# Center_Console_-_Raspberry_Pi_Interface.net
KiCad netlist of a schematic drawn in Altium Designer
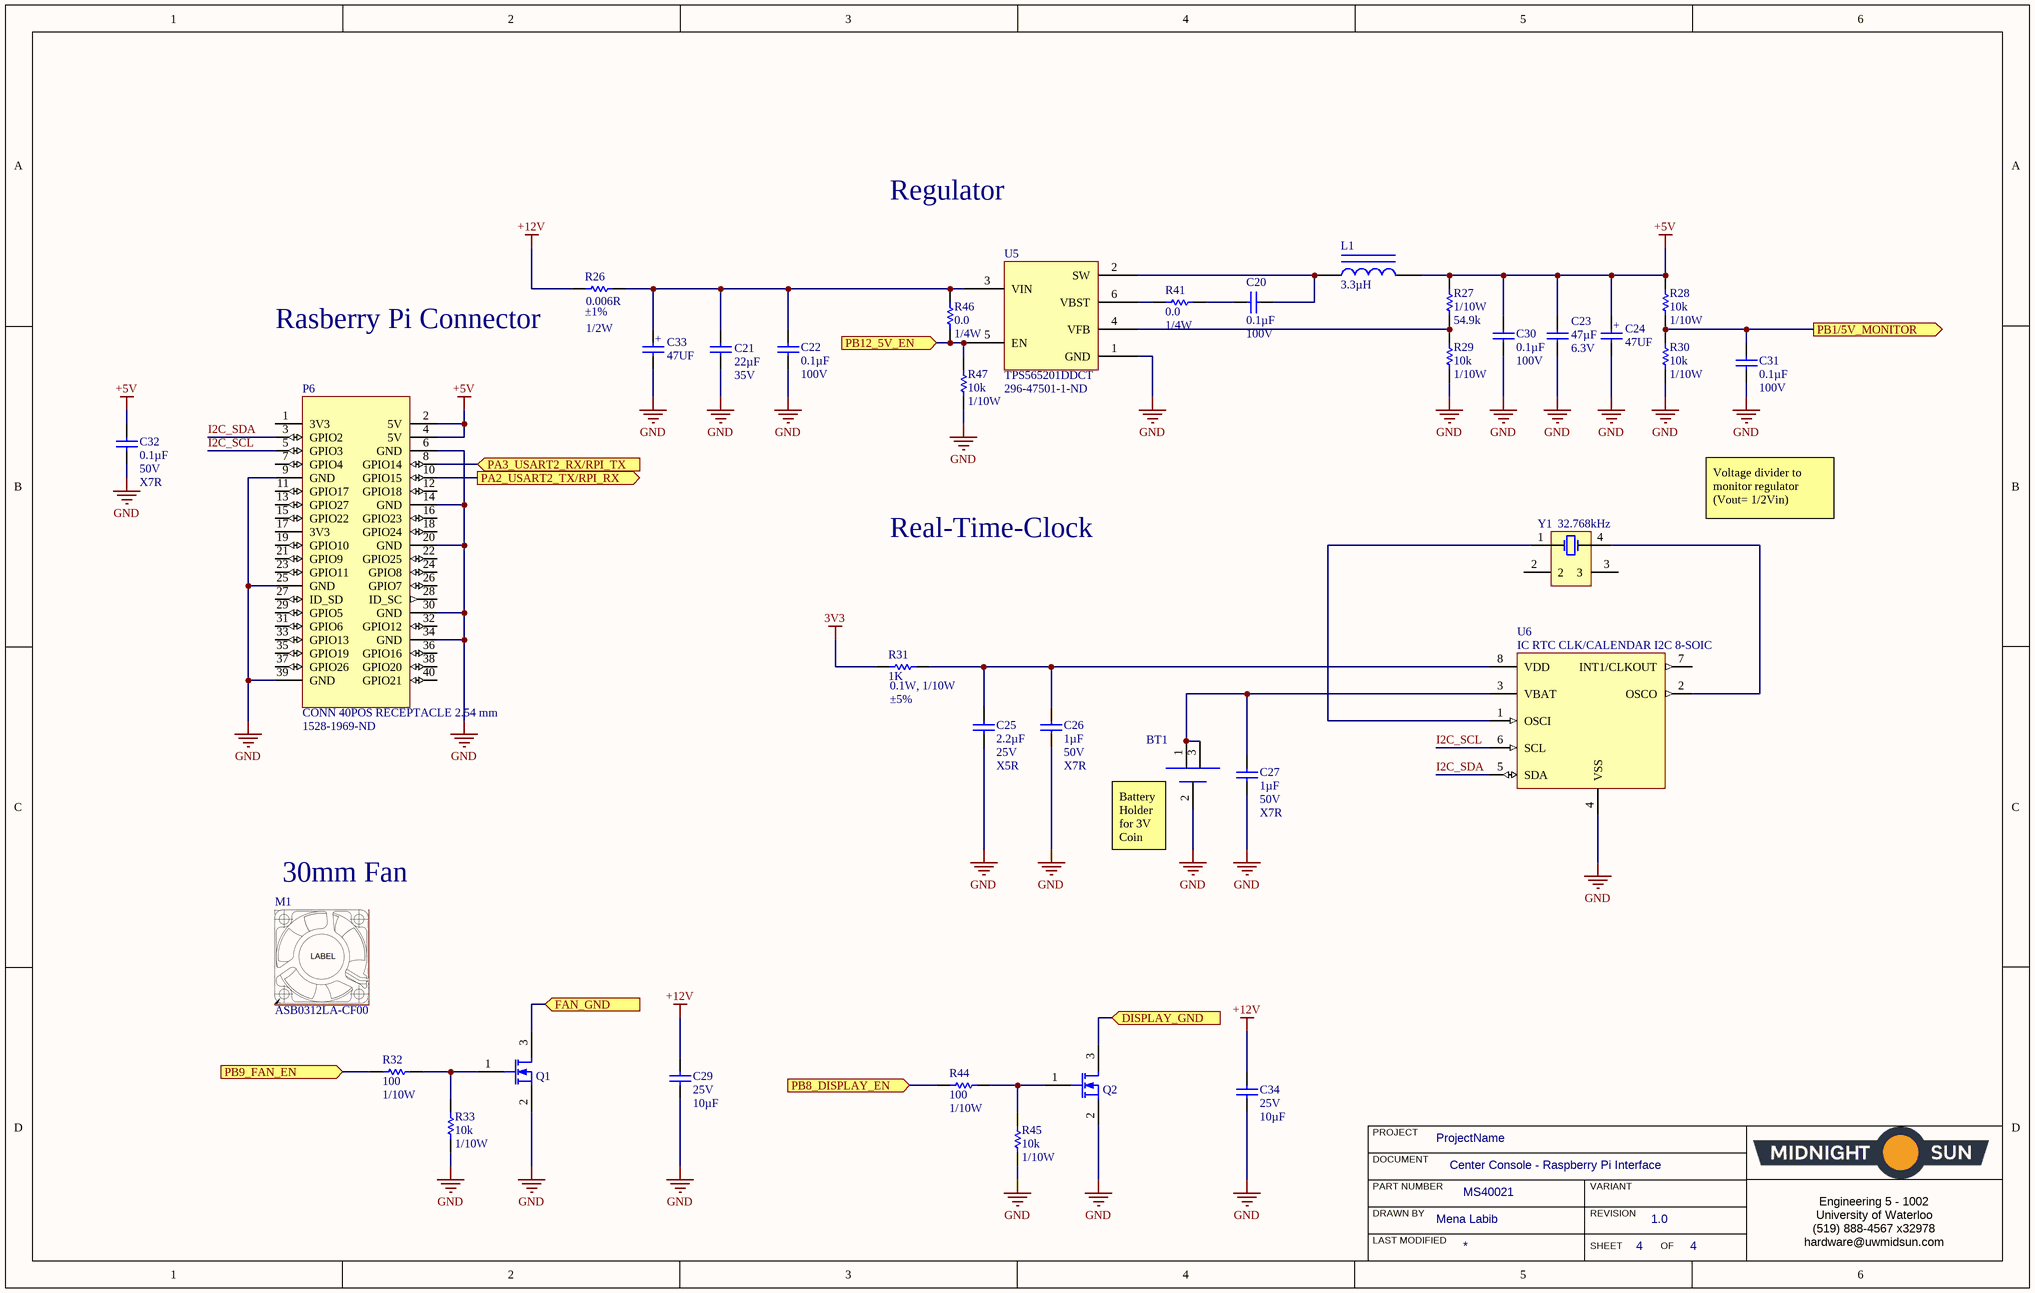
[diagram p0: Center Console - Raspberry Pi Interface.SchDoc]

(export (version "E")
  (design (tool "Eeschema 10.0.6"))
  (components
    (comp (ref "BT1")
      (value "HOLDER BATTERY COIN 12MM DIA")
      (footprint "HOLDER COIN CELL 1220 3V")
      (description "Coin cell holder smd")
      (fields
        (field (name "MANUFACTURER") "Keystone Electronics")
        (field (name "MANUFACTURER PART NUMBER") "3000")
      )
      (libsource (lib "Schematic Diagrams") (part "HOLDER BATTERY COIN 12MM DIA"))
    )
    (comp (ref "C20")
      (value "CAP CER 0.1UF 100V 10% X7R 0805")
      (footprint "CAP, 0805")
      (description "0.1µF ±10% 100V Ceramic Capacitor X7R 0805 (2012 Metric)")
      (fields
        (field (name "TOLERANCE") "±10%")
        (field (name "CAPACITANCE") "0.1µF")
        (field (name "VOLTAGE") "100V")
      )
      (libsource (lib "Schematic Diagrams") (part "CAP CER 0.1UF 100V 10% X7R 0805"))
    )
    (comp (ref "C21")
      (value "CAP CER 22UF 35V X5R 0805")
      (footprint "CAP, 0805")
      (description "22µF ±20% 35V Ceramic Capacitor X5R 0805 (2012 Metric)")
      (fields
        (field (name "MANUFACTURER") "TDK")
        (field (name "MANUFACTURER PART NUMBER") "C2012X5R1V226M125AC")
      )
      (libsource (lib "Schematic Diagrams") (part "CAP CER 22UF 35V X5R 0805"))
    )
    (comp (ref "C22")
      (value "CAP CER 0.1UF 100V 10% X7R 0805")
      (footprint "CAP, 0805")
      (description "0.1µF ±10% 100V Ceramic Capacitor X7R 0805 (2012 Metric)")
      (fields
        (field (name "TOLERANCE") "±10%")
        (field (name "CAPACITANCE") "0.1µF")
        (field (name "VOLTAGE") "100V")
      )
      (libsource (lib "Schematic Diagrams") (part "CAP CER 0.1UF 100V 10% X7R 0805"))
    )
    (comp (ref "C23")
      (value "CAP CER 47UF 6.3V X7R 1210")
      (footprint "1210")
      (description "47µF ±10% 6.3V Ceramic Capacitor X7R 1210 (3225 Metric)")
      (fields
        (field (name "MANUFACTURER") "Murata")
        (field (name "MANUFACTURER PART NUMBER") "GCJ32ER70J476KE01L")
      )
      (libsource (lib "Schematic Diagrams") (part "CAP CER 47UF 6.3V X7R 1210"))
    )
    (comp (ref "C24")
      (value "47UF")
      (footprint "CAP ALUM 6.3MM RADIAL SMD")
      (description "47µF 35V Aluminum Electrolytic Capacitors Radial, Can - SMD 1000 Hrs @ 85°C")
      (fields
        (field (name "MANUFACTURER") "Panasonic")
        (field (name "MANUFACTURER PART NUMBER") "EEE-1VA470WP")
      )
      (libsource (lib "Schematic Diagrams") (part "CAP ALUM 47UF 20% 35V SMD"))
    )
    (comp (ref "C25")
      (value "CAP CER 2.2UF 25V 10% X5R 0603")
      (footprint "CAP, 0603")
      (description "2.2µF ±10% 25V Ceramic Capacitor X5R 0603 (1608 Metric)")
      (fields
        (field (name "TOLERANCE") "±10%")
        (field (name "CAPACITANCE") "2.2µF")
        (field (name "VOLTAGE") "25V")
        (field (name "TEMPERATURE COEFFICIENT") "X5R")
      )
      (libsource (lib "Schematic Diagrams") (part "CAP CER 2.2UF 25V 10% X5R 0603"))
    )
    (comp (ref "C26")
      (value "CAP CER 1UF 50V 10% X7R 0603")
      (footprint "CAP, 0603")
      (description "1µF ±10% 50V Ceramic Capacitor X7R 0603 (1608 Metric)")
      (fields
        (field (name "TOLERANCE") "±10%")
        (field (name "CAPACITANCE") "1µF")
        (field (name "VOLTAGE") "50V")
        (field (name "TEMPERATURE COEFFICIENT") "X7R")
      )
      (libsource (lib "Schematic Diagrams") (part "CAP CER 1UF 50V 10% X7R 0603"))
    )
    (comp (ref "C27")
      (value "CAP CER 1UF 50V 10% X7R 0603")
      (footprint "CAP, 0603")
      (description "1µF ±10% 50V Ceramic Capacitor X7R 0603 (1608 Metric)")
      (fields
        (field (name "TOLERANCE") "±10%")
        (field (name "CAPACITANCE") "1µF")
        (field (name "VOLTAGE") "50V")
        (field (name "TEMPERATURE COEFFICIENT") "X7R")
      )
      (libsource (lib "Schematic Diagrams") (part "CAP CER 1UF 50V 10% X7R 0603"))
    )
    (comp (ref "C29")
      (value "CAP CER 10uF 25V 10% X5R 0805")
      (footprint "CAP, 0805")
      (description "10µF ±10% 25V Ceramic Capacitor X5R 0805 (2012 Metric)")
      (fields
        (field (name "MANUFACTURER") "Murata Electronics North America")
        (field (name "MANUFACTURER PART NUMBER") "GRM21BR61E106KA73L")
        (field (name "VOLTAGE - RATED") "25V")
        (field (name "CAPACITANCE") "10µF")
      )
      (libsource (lib "altium-import") (part "root_0_CAP CER 10uF 25V 10% X5R 0805_"))
    )
    (comp (ref "C30")
      (value "CAP CER 0.1UF 100V 10% X7R 0805")
      (footprint "CAP, 0805")
      (description "0.1µF ±10% 100V Ceramic Capacitor X7R 0805 (2012 Metric)")
      (fields
        (field (name "TOLERANCE") "±10%")
        (field (name "CAPACITANCE") "0.1µF")
        (field (name "VOLTAGE") "100V")
      )
      (libsource (lib "Schematic Diagrams") (part "CAP CER 0.1UF 100V 10% X7R 0805"))
    )
    (comp (ref "C31")
      (value "CAP CER 0.1UF 100V 10% X7R 0805")
      (footprint "CAP, 0805")
      (description "0.1µF ±10% 100V Ceramic Capacitor X7R 0805 (2012 Metric)")
      (fields
        (field (name "TOLERANCE") "±10%")
        (field (name "CAPACITANCE") "0.1µF")
        (field (name "VOLTAGE") "100V")
      )
      (libsource (lib "Schematic Diagrams") (part "CAP CER 0.1UF 100V 10% X7R 0805"))
    )
    (comp (ref "C32")
      (value "CAP CER 0.1UF 50V 10% X7R 0603")
      (footprint "CAP, 0603")
      (description "0.10µF ±10% 50V Ceramic Capacitor X7R 0603 (1608 Metric)")
      (fields
        (field (name "TOLERANCE") "±10%")
        (field (name "CAPACITANCE") "0.1µF")
        (field (name "VOLTAGE") "50V")
        (field (name "TEMPERATURE COEFFICIENT") "X7R")
      )
      (libsource (lib "Schematic Diagrams") (part "CAP CER 0.1UF 50V 10% X7R 0603"))
    )
    (comp (ref "C33")
      (value "47UF")
      (footprint "CAP ALUM 6.3MM RADIAL SMD")
      (description "47µF 35V Aluminum Electrolytic Capacitors Radial, Can - SMD 1000 Hrs @ 85°C")
      (fields
        (field (name "MANUFACTURER") "Panasonic")
        (field (name "MANUFACTURER PART NUMBER") "EEE-1VA470WP")
      )
      (libsource (lib "Schematic Diagrams") (part "CAP ALUM 47UF 20% 35V SMD"))
    )
    (comp (ref "C34")
      (value "CAP CER 10uF 25V 10% X5R 0805")
      (footprint "CAP, 0805")
      (description "10µF ±10% 25V Ceramic Capacitor X5R 0805 (2012 Metric)")
      (fields
        (field (name "MANUFACTURER") "Murata Electronics North America")
        (field (name "MANUFACTURER PART NUMBER") "GRM21BR61E106KA73L")
        (field (name "VOLTAGE - RATED") "25V")
        (field (name "CAPACITANCE") "10µF")
      )
      (libsource (lib "altium-import") (part "root_0_CAP CER 10uF 25V 10% X5R 0805_"))
    )
    (comp (ref "L1")
      (value "IND 3.3uH 5.2A 20MOHM SMD")
      (footprint "IND 3.3UH 5.2A 20 MOHM SMD VLP8040")
      (description "3.3µH Shielded Wirewound Inductor 5.2A 20 mOhm Max Nonstandard")
      (fields
        (field (name "MANUFACTURER") "TDK Corporation")
        (field (name "MANUFACTURER PART NUMBER") "VLS201612CX-3R3M")
        (field (name "INDUCTANCE") "3.3µH")
      )
      (libsource (lib "Schematic Diagrams") (part "IND 3.3uH 5.2A 20MOHM SMD"))
    )
    (comp (ref "M1")
      (value "FAN AXIAL 30x10MM 12VDC")
      (footprint "FAN AXIAL 30x10MM 12VDC")
      (description "FAN AXIAL 30X10MM 12VDC WIRE")
      (fields
        (field (name "MANUFACTURER") "Delta Design")
        (field (name "MANUFACTURER PART NUMBER") "ASB0312LA-CF00")
      )
      (libsource (lib "altium-import") (part "root_0_FAN AXIAL 30x10MM 12VDC_"))
    )
    (comp (ref "P6")
      (value "CONN 40POS RECEPTACLE 2.54 mm")
      (footprint "CONN 40POS RECEPTACLE 2.54 MM")
      (description "GPIO HEADER FOR RASPBERRYPI A+/B")
      (fields
        (field (name "MANUFACTURER") "Adafruit Industries")
        (field (name "MANUFACTURER PART NUMBER") "1992")
        (field (name "SUPPLIER PART NUMBER 1") "1528-1969-ND")
      )
      (libsource (lib "Schematic Diagrams") (part "CONN 40POS RECEPTACLE 2.54 mm"))
    )
    (comp (ref "Q1")
      (value "MOSFET N-CH 30V 6.2A 0.9W SOT-23")
      (footprint "MOSFET N-CH 30V 6.2A 0.9W SOT-23")
      (description "N-Channel 30V 6.2A (Ta) 900mW (Ta) Surface Mount SOT-23")
      (fields (field (name "MANUFACTURER") "Diodes") (field (name "MANUFACTURER PART NUMBER") "DMN3023L-7"))
      (libsource (lib "altium-import") (part "root_0_MOSFET N-CH 30V 6.2A 0.9W SOT-23_"))
    )
    (comp (ref "Q2")
      (value "MOSFET N-CH 30V 6.2A 0.9W SOT-23")
      (footprint "MOSFET N-CH 30V 6.2A 0.9W SOT-23")
      (description "N-Channel 30V 6.2A (Ta) 900mW (Ta) Surface Mount SOT-23")
      (fields (field (name "MANUFACTURER") "Diodes") (field (name "MANUFACTURER PART NUMBER") "DMN3023L-7"))
      (libsource (lib "altium-import") (part "root_0_MOSFET N-CH 30V 6.2A 0.9W SOT-23_"))
    )
    (comp (ref "R26")
      (value "RES 0.006 OHM 1% 1/2W 1206")
      (footprint "RES 1206")
      (fields
        (field (name "TOLERANCE") "±1%")
        (field (name "MANUFACTURER") "Panasonic Electronic Components")
        (field (name "MANUFACTURER PART NUMBER") "ERJ-MP2KF6M0U")
        (field (name "RESISTANCE (OHMS)") "0.006R")
        (field (name "POWER (WATTS)") "1/2W")
      )
      (libsource (lib "Schematic Diagrams") (part "RES 0.006 OHM 1% 1/2W 1206"))
    )
    (comp (ref "R27")
      (value "RES 54.9K OHM 1% 1/10W 0603")
      (footprint "RES, 0603")
      (description "54.9k Ohm ±1% 0.1W, 1/10W Chip Resistor 0603 (1608 Metric) Automotive AEC-Q200 Thick Film")
      (fields
        (field (name "MANUFACTURER") "Panasonic Electronic Components")
        (field (name "MANUFACTURER PART NUMBER") "ERJ-3EKF5492V")
        (field (name "POWER (WATTS)") "1/10W")
        (field (name "RESISTANCE (OHMS)") "54.9k")
      )
      (libsource (lib "Schematic Diagrams") (part "RES 54.9K OHM 1% 1/10W 0603"))
    )
    (comp (ref "R28")
      (value "RES 10K OHM 1% 1/10W 0603")
      (footprint "RES, 0603")
      (description "RES SMD 10K OHM 1% 1/10W 0603")
      (fields
        (field (name "TOLERANCE") "±1%")
        (field (name "RESISTANCE") "10k")
        (field (name "POWER") "1/10W")
      )
      (libsource (lib "Schematic Diagrams") (part "RES 10K OHM 1% 1/10W 0603"))
    )
    (comp (ref "R29")
      (value "RES 10K OHM 1% 1/10W 0603")
      (footprint "RES, 0603")
      (description "RES SMD 10K OHM 1% 1/10W 0603")
      (fields
        (field (name "TOLERANCE") "±1%")
        (field (name "RESISTANCE") "10k")
        (field (name "POWER") "1/10W")
      )
      (libsource (lib "Schematic Diagrams") (part "RES 10K OHM 1% 1/10W 0603"))
    )
    (comp (ref "R30")
      (value "RES 10K OHM 1% 1/10W 0603")
      (footprint "RES, 0603")
      (description "RES SMD 10K OHM 1% 1/10W 0603")
      (fields
        (field (name "TOLERANCE") "±1%")
        (field (name "RESISTANCE") "10k")
        (field (name "POWER") "1/10W")
      )
      (libsource (lib "Schematic Diagrams") (part "RES 10K OHM 1% 1/10W 0603"))
    )
    (comp (ref "R31")
      (value "1K")
      (footprint "RES, 0603")
      (description "1k Ohm ±5% 0.1W, 1/10W Chip Resistor 0603 (1608 Metric)")
      (fields
        (field (name "MANUFACTURER") "Yageo")
        (field (name "MANUFACTURER PART NUMBER") "RC0603JR-071KL")
        (field (name "TOLERANCE") "±5%")
        (field (name "POWER (WATTS)") "0.1W, 1/10W")
      )
      (libsource (lib "Schematic Diagrams") (part "RES 1K OHM 5% 1/10W 0603"))
    )
    (comp (ref "R32")
      (value "RES 100 OHM 1% 1/10W 0603")
      (footprint "RES, 0603")
      (description "100 Ohm ±1% 0.1W, 1/10W Chip Resistor 0603 (1608 Metric) Moisture Resistant Thick Film")
      (fields
        (field (name "TOLERANCE") "±1%")
        (field (name "RESISTANCE") "100")
        (field (name "POWER") "1/10W")
      )
      (libsource (lib "altium-import") (part "root_1_RES 100 OHM 1% 1/10W 0603_"))
    )
    (comp (ref "R33")
      (value "RES 10K OHM 1% 1/10W 0603")
      (footprint "RES, 0603")
      (description "RES SMD 10K OHM 1% 1/10W 0603")
      (fields
        (field (name "TOLERANCE") "±1%")
        (field (name "RESISTANCE") "10k")
        (field (name "POWER") "1/10W")
      )
      (libsource (lib "altium-import") (part "root_0_RES 10K OHM 1% 1/10W 0603_"))
    )
    (comp (ref "R41")
      (value "RES 0.0 OHM 1/4W 0603")
      (footprint "RES, 0603")
      (description "RES SMD 0.0 OHM JUMPER 1/4W 0603")
      (fields (field (name "RESISTANCE") "0.0") (field (name "POWER (WATTS)") "1/4W"))
      (libsource (lib "Schematic Diagrams") (part "RES 0.0 OHM 1/4W 0603"))
    )
    (comp (ref "R44")
      (value "RES 100 OHM 1% 1/10W 0603")
      (footprint "RES, 0603")
      (description "100 Ohm ±1% 0.1W, 1/10W Chip Resistor 0603 (1608 Metric) Moisture Resistant Thick Film")
      (fields
        (field (name "TOLERANCE") "±1%")
        (field (name "RESISTANCE") "100")
        (field (name "POWER") "1/10W")
      )
      (libsource (lib "altium-import") (part "root_1_RES 100 OHM 1% 1/10W 0603_"))
    )
    (comp (ref "R45")
      (value "RES 10K OHM 1% 1/10W 0603")
      (footprint "RES, 0603")
      (description "RES SMD 10K OHM 1% 1/10W 0603")
      (fields
        (field (name "TOLERANCE") "±1%")
        (field (name "RESISTANCE") "10k")
        (field (name "POWER") "1/10W")
      )
      (libsource (lib "altium-import") (part "root_0_RES 10K OHM 1% 1/10W 0603_"))
    )
    (comp (ref "R46")
      (value "RES 0.0 OHM 1/4W 0603")
      (footprint "RES, 0603")
      (description "RES SMD 0.0 OHM JUMPER 1/4W 0603")
      (fields (field (name "RESISTANCE") "0.0") (field (name "POWER (WATTS)") "1/4W"))
      (libsource (lib "Schematic Diagrams") (part "RES 0.0 OHM 1/4W 0603"))
    )
    (comp (ref "R47")
      (value "RES 10K OHM 1% 1/10W 0603")
      (footprint "RES, 0603")
      (description "RES SMD 10K OHM 1% 1/10W 0603")
      (fields
        (field (name "TOLERANCE") "±1%")
        (field (name "RESISTANCE") "10k")
        (field (name "POWER") "1/10W")
      )
      (libsource (lib "Schematic Diagrams") (part "RES 10K OHM 1% 1/10W 0603"))
    )
    (comp (ref "U5")
      (value "IC REG BUCK 4.5V TO 17V, 5A, SYNCHRONOUS STE")
      (footprint "IC REG BUCK 4.5V TO 17V, 5A")
      (description "Buck Switching Regulator IC Positive Adjustable 0.6V 1 Output 5A SOT-23-6 Thin, TSOT-23-6")
      (fields
        (field (name "MANUFACTURER") "Texas Instruments")
        (field (name "MANUFACTURER PART NUMBER") "TPS565201DDCT")
        (field (name "SUPPLIER PART NUMBER 1") "296-47501-1-ND")
      )
      (libsource (lib "Schematic Diagrams") (part "IC REG BUCK 4.5V TO 17V, 5A, SYNCHRONOUS STE"))
    )
    (comp (ref "U6")
      (value "IC RTC CLK/CALENDAR I2C 8-SOIC")
      (footprint "SOIC8")
      (description "Real Time Clock (RTC) IC Clock/Calendar I²C, 2-Wire Serial 8-SOIC (0.154\", 3.90mm Width)")
      (fields
        (field (name "MANUFACTURER") "NXP Semiconductors")
        (field (name "MANUFACTURER PART NUMBER") "PCF8523T/1,118")
      )
      (libsource (lib "Schematic Diagrams") (part "IC RTC CLK/CALENDAR I2C 8-SOIC"))
    )
    (comp (ref "Y1")
      (value "CRYSTAL 32.7680KHZ 12.5PF SMD")
      (footprint "4-SOJ")
      (description "32.768kHz ±20ppm Crystal 12.5pF 50 kOhms 4-SOJ, 5.50mm pitch")
      (fields
        (field (name "MANUFACTURER") "ECS International")
        (field (name "MANUFACTURER PART NUMBER") "ECS-.327-12.5-17X-TR")
        (field (name "FREQUENCY") "32.768kHz")
      )
      (libsource (lib "Schematic Diagrams") (part "CRYSTAL 32.7680KHZ 12.5PF SMD"))
    )
  )
  (nets
    (net (code "1") (name "+5V") (class "Default")
      (node (ref "C23") (pin "1") (pinfunction "1_1") (pintype "passive"))
      (node (ref "C24") (pin "1") (pinfunction "1_1") (pintype "passive"))
      (node (ref "C30") (pin "1") (pinfunction "1_1") (pintype "passive"))
      (node (ref "C32") (pin "1") (pinfunction "1_1") (pintype "passive"))
      (node (ref "L1") (pin "2") (pinfunction "2_2") (pintype "passive"))
      (node (ref "P6") (pin "2") (pinfunction "5V_2") (pintype "power_in"))
      (node (ref "P6") (pin "4") (pinfunction "5V_4") (pintype "power_in"))
      (node (ref "R27") (pin "1") (pinfunction "1_1") (pintype "passive"))
      (node (ref "R28") (pin "1") (pinfunction "1_1") (pintype "passive"))
    )
    (net (code "2") (name "+12V") (class "Default")
      (node (ref "C29") (pin "1") (pinfunction "1_1") (pintype "passive"))
      (node (ref "C34") (pin "1") (pinfunction "1_1") (pintype "passive"))
      (node (ref "R26") (pin "1") (pinfunction "1_1") (pintype "passive"))
    )
    (net (code "3") (name "/DISPLAY_GND") (class "Default")
      (node (ref "Q2") (pin "3") (pinfunction "D_3") (pintype "passive"))
    )
    (net (code "4") (name "/FAN_GND") (class "Default")
      (node (ref "Q1") (pin "3") (pinfunction "D_3") (pintype "passive"))
    )
    (net (code "5") (name "/I2C_SCL") (class "Default")
      (node (ref "P6") (pin "5") (pinfunction "GPIO3_5") (pintype "bidirectional"))
      (node (ref "U6") (pin "6") (pinfunction "SCL_6") (pintype "input"))
    )
    (net (code "6") (name "/I2C_SDA") (class "Default")
      (node (ref "P6") (pin "3") (pinfunction "GPIO2_3") (pintype "bidirectional"))
      (node (ref "U6") (pin "5") (pinfunction "SDA_5") (pintype "bidirectional"))
    )
    (net (code "7") (name "/PA2_USART2_TX{slash}RPI_RX") (class "Default")
      (node (ref "P6") (pin "10") (pinfunction "GPIO15_10") (pintype "bidirectional"))
    )
    (net (code "8") (name "/PA3_USART2_RX{slash}RPI_TX") (class "Default")
      (node (ref "P6") (pin "8") (pinfunction "GPIO14_8") (pintype "bidirectional"))
    )
    (net (code "9") (name "/PB1{slash}5V_MONITOR") (class "Default")
      (node (ref "C31") (pin "1") (pinfunction "1_1") (pintype "passive"))
      (node (ref "R28") (pin "2") (pinfunction "2_2") (pintype "passive"))
      (node (ref "R30") (pin "1") (pinfunction "1_1") (pintype "passive"))
    )
    (net (code "10") (name "/PB8_DISPLAY_EN") (class "Default")
      (node (ref "R44") (pin "1") (pinfunction "1_1") (pintype "passive"))
    )
    (net (code "11") (name "/PB9_FAN_EN") (class "Default")
      (node (ref "R32") (pin "1") (pinfunction "1_1") (pintype "passive"))
    )
    (net (code "12") (name "/PB12_5V_EN") (class "Default")
      (node (ref "R46") (pin "2") (pinfunction "2_2") (pintype "passive"))
      (node (ref "R47") (pin "1") (pinfunction "1_1") (pintype "passive"))
      (node (ref "U5") (pin "5") (pinfunction "EN_5") (pintype "passive"))
    )
    (net (code "13") (name "3V3") (class "Default")
      (node (ref "R31") (pin "1") (pinfunction "1_1") (pintype "passive"))
    )
    (net (code "14") (name "GND") (class "Default")
      (node (ref "BT1") (pin "2") (pinfunction "negative_2") (pintype "power_in"))
      (node (ref "C21") (pin "2") (pinfunction "2_2") (pintype "passive"))
      (node (ref "C22") (pin "2") (pinfunction "2_2") (pintype "passive"))
      (node (ref "C23") (pin "2") (pinfunction "2_2") (pintype "passive"))
      (node (ref "C24") (pin "2") (pinfunction "2_2") (pintype "passive"))
      (node (ref "C25") (pin "2") (pinfunction "2_2") (pintype "passive"))
      (node (ref "C26") (pin "2") (pinfunction "2_2") (pintype "passive"))
      (node (ref "C27") (pin "2") (pinfunction "2_2") (pintype "passive"))
      (node (ref "C29") (pin "2") (pinfunction "2_2") (pintype "passive"))
      (node (ref "C30") (pin "2") (pinfunction "2_2") (pintype "passive"))
      (node (ref "C31") (pin "2") (pinfunction "2_2") (pintype "passive"))
      (node (ref "C32") (pin "2") (pinfunction "2_2") (pintype "passive"))
      (node (ref "C33") (pin "2") (pinfunction "2_2") (pintype "passive"))
      (node (ref "C34") (pin "2") (pinfunction "2_2") (pintype "passive"))
      (node (ref "P6") (pin "14") (pinfunction "GND_14") (pintype "power_in"))
      (node (ref "P6") (pin "20") (pinfunction "GND_20") (pintype "power_in"))
      (node (ref "P6") (pin "25") (pinfunction "GND_25") (pintype "power_in"))
      (node (ref "P6") (pin "30") (pinfunction "GND_30") (pintype "power_in"))
      (node (ref "P6") (pin "34") (pinfunction "GND_34") (pintype "power_in"))
      (node (ref "P6") (pin "39") (pinfunction "GND_39") (pintype "power_in"))
      (node (ref "P6") (pin "6") (pinfunction "GND_6") (pintype "power_in"))
      (node (ref "P6") (pin "9") (pinfunction "GND_9") (pintype "power_in"))
      (node (ref "Q1") (pin "2") (pinfunction "S_2") (pintype "passive"))
      (node (ref "Q2") (pin "2") (pinfunction "S_2") (pintype "passive"))
      (node (ref "R29") (pin "2") (pinfunction "2_2") (pintype "passive"))
      (node (ref "R30") (pin "2") (pinfunction "2_2") (pintype "passive"))
      (node (ref "R33") (pin "2") (pinfunction "2_2") (pintype "passive"))
      (node (ref "R45") (pin "2") (pinfunction "2_2") (pintype "passive"))
      (node (ref "R47") (pin "2") (pinfunction "2_2") (pintype "passive"))
      (node (ref "U5") (pin "1") (pinfunction "GND_1") (pintype "passive"))
      (node (ref "U6") (pin "4") (pinfunction "VSS_4") (pintype "passive"))
    )
    (net (code "15") (name "Net-(BT1-positive_1)") (class "Default")
      (node (ref "BT1") (pin "1") (pinfunction "positive_1_1") (pintype "power_in"))
      (node (ref "BT1") (pin "3") (pinfunction "positive_2_3") (pintype "power_in"))
      (node (ref "C27") (pin "1") (pinfunction "1_1") (pintype "passive"))
      (node (ref "U6") (pin "3") (pinfunction "VBAT_3") (pintype "power_in"))
    )
    (net (code "16") (name "Net-(C20-Pad1)") (class "Default")
      (node (ref "C20") (pin "1") (pinfunction "1_1") (pintype "passive"))
      (node (ref "R41") (pin "2") (pinfunction "2_2") (pintype "passive"))
    )
    (net (code "17") (name "Net-(Q1-G)") (class "Default")
      (node (ref "Q1") (pin "1") (pinfunction "G_1") (pintype "passive"))
      (node (ref "R32") (pin "2") (pinfunction "2_2") (pintype "passive"))
      (node (ref "R33") (pin "1") (pinfunction "1_1") (pintype "passive"))
    )
    (net (code "18") (name "Net-(Q2-G)") (class "Default")
      (node (ref "Q2") (pin "1") (pinfunction "G_1") (pintype "passive"))
      (node (ref "R44") (pin "2") (pinfunction "2_2") (pintype "passive"))
      (node (ref "R45") (pin "1") (pinfunction "1_1") (pintype "passive"))
    )
    (net (code "19") (name "Net-(U5-SW)") (class "Default")
      (node (ref "C20") (pin "2") (pinfunction "2_2") (pintype "passive"))
      (node (ref "L1") (pin "1") (pinfunction "1_1") (pintype "passive"))
      (node (ref "U5") (pin "2") (pinfunction "SW_2") (pintype "passive"))
    )
    (net (code "20") (name "Net-(U5-VBST)") (class "Default")
      (node (ref "R41") (pin "1") (pinfunction "1_1") (pintype "passive"))
      (node (ref "U5") (pin "6") (pinfunction "VBST_6") (pintype "passive"))
    )
    (net (code "21") (name "Net-(U5-VFB)") (class "Default")
      (node (ref "R27") (pin "2") (pinfunction "2_2") (pintype "passive"))
      (node (ref "R29") (pin "1") (pinfunction "1_1") (pintype "passive"))
      (node (ref "U5") (pin "4") (pinfunction "VFB_4") (pintype "passive"))
    )
    (net (code "22") (name "Net-(U5-VIN)") (class "Default")
      (node (ref "C21") (pin "1") (pinfunction "1_1") (pintype "passive"))
      (node (ref "C22") (pin "1") (pinfunction "1_1") (pintype "passive"))
      (node (ref "C33") (pin "1") (pinfunction "1_1") (pintype "passive"))
      (node (ref "R26") (pin "2") (pinfunction "2_2") (pintype "passive"))
      (node (ref "R46") (pin "1") (pinfunction "1_1") (pintype "passive"))
      (node (ref "U5") (pin "3") (pinfunction "VIN_3") (pintype "passive"))
    )
    (net (code "23") (name "Net-(U6-OSCI)") (class "Default")
      (node (ref "U6") (pin "1") (pinfunction "OSCI_1") (pintype "input"))
      (node (ref "Y1") (pin "1") (pinfunction "1_1") (pintype "passive"))
    )
    (net (code "24") (name "Net-(U6-OSCO)") (class "Default")
      (node (ref "U6") (pin "2") (pinfunction "OSCO_2") (pintype "output"))
      (node (ref "Y1") (pin "4") (pinfunction "4_4") (pintype "passive"))
    )
    (net (code "25") (name "Net-(U6-VDD)") (class "Default")
      (node (ref "C25") (pin "1") (pinfunction "1_1") (pintype "passive"))
      (node (ref "C26") (pin "1") (pinfunction "1_1") (pintype "passive"))
      (node (ref "R31") (pin "2") (pinfunction "2_2") (pintype "passive"))
      (node (ref "U6") (pin "8") (pinfunction "VDD_8") (pintype "power_in"))
    )
    (net (code "26") (name "unconnected-(P6-3V3-Pad1)") (class "Default")
      (node (ref "P6") (pin "1") (pinfunction "3V3_1") (pintype "power_in"))
    )
    (net (code "27") (name "unconnected-(P6-3V3-Pad17)") (class "Default")
      (node (ref "P6") (pin "17") (pinfunction "3V3_17") (pintype "power_in"))
    )
    (net (code "28") (name "unconnected-(P6-GPIO4-Pad7)") (class "Default")
      (node (ref "P6") (pin "7") (pinfunction "GPIO4_7") (pintype "bidirectional"))
    )
    (net (code "29") (name "unconnected-(P6-GPIO5-Pad29)") (class "Default")
      (node (ref "P6") (pin "29") (pinfunction "GPIO5_29") (pintype "bidirectional"))
    )
    (net (code "30") (name "unconnected-(P6-GPIO6-Pad31)") (class "Default")
      (node (ref "P6") (pin "31") (pinfunction "GPIO6_31") (pintype "bidirectional"))
    )
    (net (code "31") (name "unconnected-(P6-GPIO7-Pad26)") (class "Default")
      (node (ref "P6") (pin "26") (pinfunction "GPIO7_26") (pintype "bidirectional"))
    )
    (net (code "32") (name "unconnected-(P6-GPIO8-Pad24)") (class "Default")
      (node (ref "P6") (pin "24") (pinfunction "GPIO8_24") (pintype "bidirectional"))
    )
    (net (code "33") (name "unconnected-(P6-GPIO9-Pad21)") (class "Default")
      (node (ref "P6") (pin "21") (pinfunction "GPIO9_21") (pintype "bidirectional"))
    )
    (net (code "34") (name "unconnected-(P6-GPIO10-Pad19)") (class "Default")
      (node (ref "P6") (pin "19") (pinfunction "GPIO10_19") (pintype "bidirectional"))
    )
    (net (code "35") (name "unconnected-(P6-GPIO11-Pad23)") (class "Default")
      (node (ref "P6") (pin "23") (pinfunction "GPIO11_23") (pintype "bidirectional"))
    )
    (net (code "36") (name "unconnected-(P6-GPIO12-Pad32)") (class "Default")
      (node (ref "P6") (pin "32") (pinfunction "GPIO12_32") (pintype "bidirectional"))
    )
    (net (code "37") (name "unconnected-(P6-GPIO13-Pad33)") (class "Default")
      (node (ref "P6") (pin "33") (pinfunction "GPIO13_33") (pintype "bidirectional"))
    )
    (net (code "38") (name "unconnected-(P6-GPIO16-Pad36)") (class "Default")
      (node (ref "P6") (pin "36") (pinfunction "GPIO16_36") (pintype "bidirectional"))
    )
    (net (code "39") (name "unconnected-(P6-GPIO17-Pad11)") (class "Default")
      (node (ref "P6") (pin "11") (pinfunction "GPIO17_11") (pintype "bidirectional"))
    )
    (net (code "40") (name "unconnected-(P6-GPIO18-Pad12)") (class "Default")
      (node (ref "P6") (pin "12") (pinfunction "GPIO18_12") (pintype "bidirectional"))
    )
    (net (code "41") (name "unconnected-(P6-GPIO19-Pad35)") (class "Default")
      (node (ref "P6") (pin "35") (pinfunction "GPIO19_35") (pintype "bidirectional"))
    )
    (net (code "42") (name "unconnected-(P6-GPIO20-Pad38)") (class "Default")
      (node (ref "P6") (pin "38") (pinfunction "GPIO20_38") (pintype "bidirectional"))
    )
    (net (code "43") (name "unconnected-(P6-GPIO21-Pad40)") (class "Default")
      (node (ref "P6") (pin "40") (pinfunction "GPIO21_40") (pintype "bidirectional"))
    )
    (net (code "44") (name "unconnected-(P6-GPIO22-Pad15)") (class "Default")
      (node (ref "P6") (pin "15") (pinfunction "GPIO22_15") (pintype "bidirectional"))
    )
    (net (code "45") (name "unconnected-(P6-GPIO23-Pad16)") (class "Default")
      (node (ref "P6") (pin "16") (pinfunction "GPIO23_16") (pintype "bidirectional"))
    )
    (net (code "46") (name "unconnected-(P6-GPIO24-Pad18)") (class "Default")
      (node (ref "P6") (pin "18") (pinfunction "GPIO24_18") (pintype "bidirectional"))
    )
    (net (code "47") (name "unconnected-(P6-GPIO25-Pad22)") (class "Default")
      (node (ref "P6") (pin "22") (pinfunction "GPIO25_22") (pintype "bidirectional"))
    )
    (net (code "48") (name "unconnected-(P6-GPIO26-Pad37)") (class "Default")
      (node (ref "P6") (pin "37") (pinfunction "GPIO26_37") (pintype "bidirectional"))
    )
    (net (code "49") (name "unconnected-(P6-GPIO27-Pad13)") (class "Default")
      (node (ref "P6") (pin "13") (pinfunction "GPIO27_13") (pintype "bidirectional"))
    )
    (net (code "50") (name "unconnected-(P6-ID_SC-Pad28)") (class "Default")
      (node (ref "P6") (pin "28") (pinfunction "ID_SC_28") (pintype "output"))
    )
    (net (code "51") (name "unconnected-(P6-ID_SD-Pad27)") (class "Default")
      (node (ref "P6") (pin "27") (pinfunction "ID_SD_27") (pintype "bidirectional"))
    )
    (net (code "52") (name "unconnected-(U6-INT1{slash}CLKOUT-Pad7)") (class "Default")
      (node (ref "U6") (pin "7") (pinfunction "INT1/CLKOUT_7") (pintype "output"))
    )
    (net (code "53") (name "unconnected-(Y1-Pad2)") (class "Default")
      (node (ref "Y1") (pin "2") (pinfunction "2_2") (pintype "passive"))
    )
    (net (code "54") (name "unconnected-(Y1-Pad3)") (class "Default")
      (node (ref "Y1") (pin "3") (pinfunction "3_3") (pintype "passive"))
    )
  )
)
